# BSPD.net
KiCad netlist of a schematic drawn in Altium Designer
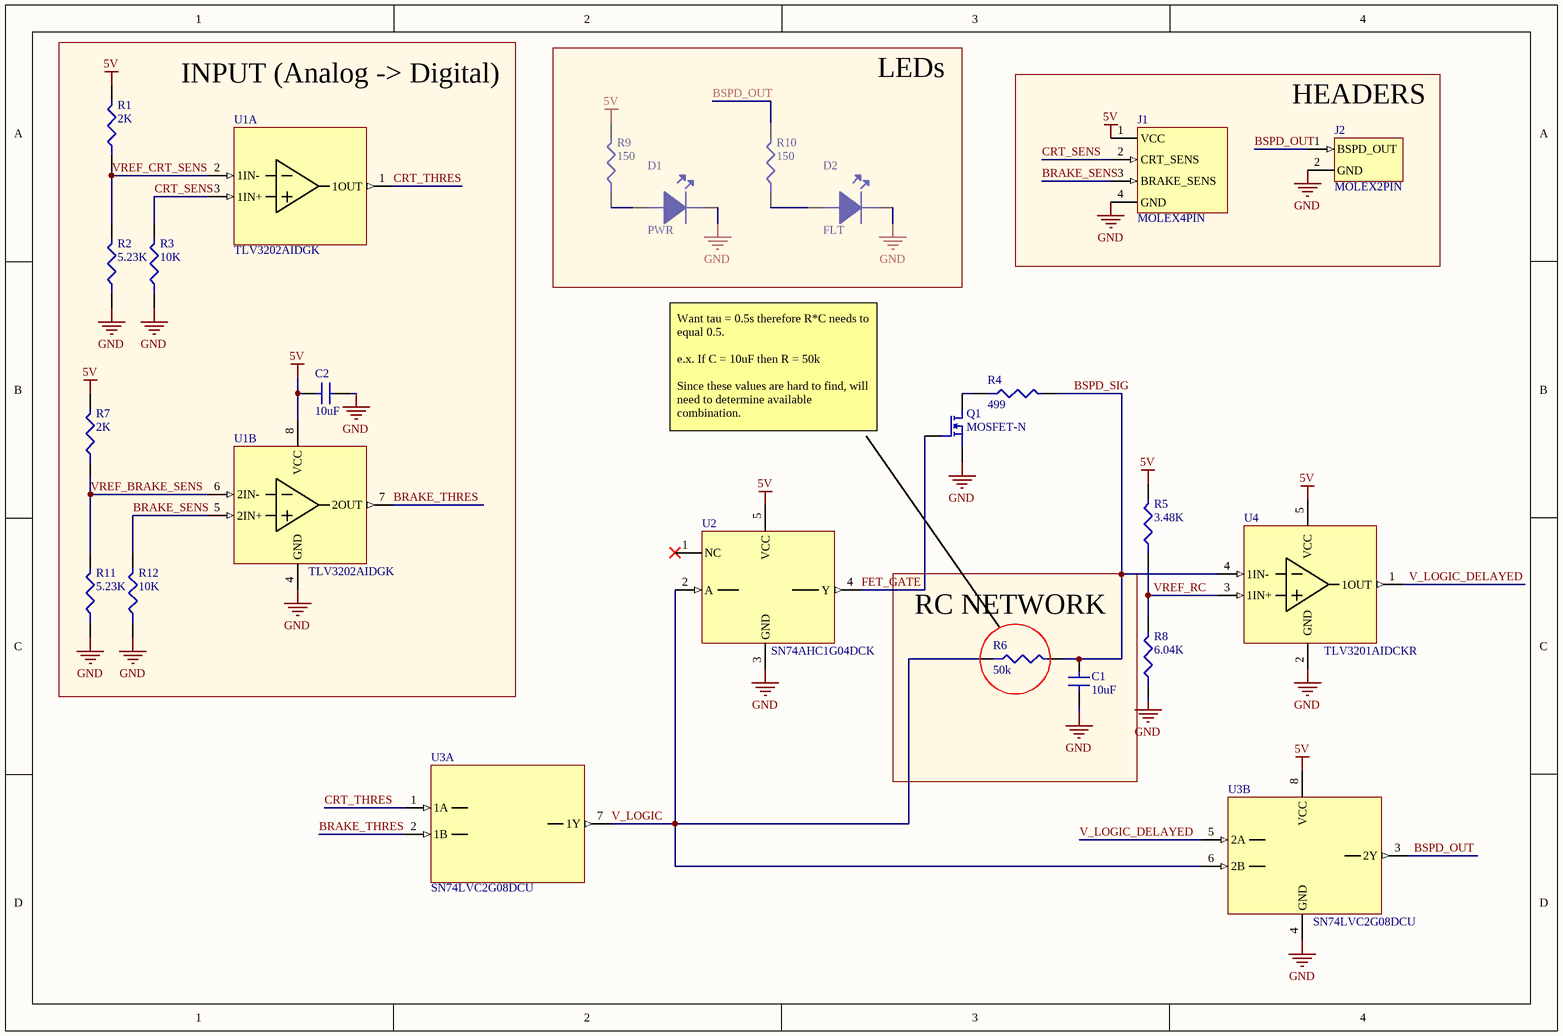
[diagram p0: BSPD.SchDoc]

(export (version "E")
  (design (tool "Eeschema 10.0.6"))
  (components
    (comp (ref "C1")
      (value "10uF")
      (footprint "C0805")
      (description "Cap Ceramic 10uF 10V X5R 10% SMD 0805 85C Embossed T/R")
      (fields
        (field (name "MANUFACTURER") "Samsung")
        (field (name "MANUFACTURER PART NUMBER") "CL21A106KPFNNNG")
      )
      (libsource (lib "BSPD") (part "CL21A106KPFNNNG"))
    )
    (comp (ref "C2")
      (value "10uF")
      (footprint "C0805")
      (description "Cap Ceramic 10uF 10V X5R 10% SMD 0805 85C Embossed T/R")
      (fields
        (field (name "MANUFACTURER") "Samsung")
        (field (name "MANUFACTURER PART NUMBER") "CL21A106KPFNNNG")
      )
      (libsource (lib "BSPD") (part "CL21A106KPFNNNG"))
    )
    (comp (ref "D1")
      (value "PWR")
      (footprint "LED_0603")
      (description "LED GREEN CLEAR SMD")
      (fields
        (field (name "MANUFACTURER") "Vishay Lite-On")
        (field (name "MANUFACTURER PART NUMBER") "LTST-C191KGKT")
      )
      (libsource (lib "BSPD") (part "LTST-C191KGKT"))
    )
    (comp (ref "D2")
      (value "FLT")
      (footprint "LED_0603")
      (description "LED RED CLEAR SMD")
      (fields
        (field (name "MANUFACTURER") "Vishay Lite-On")
        (field (name "MANUFACTURER PART NUMBER") "LTST-C191KRKT")
      )
      (libsource (lib "BSPD") (part "LTST-C191KRKT"))
    )
    (comp (ref "J1")
      (value "MOLEX4PIN")
      (footprint "MOLEX_4PIN")
      (fields (field (name "MANUFACTURER") "Molex") (field (name "MANUFACTURER PART NUMBER") "43650-0400"))
      (libsource (lib "BSPD") (part "43650-0400"))
    )
    (comp (ref "J2")
      (value "MOLEX2PIN")
      (footprint "MOLEX_2PIN")
      (description "Headers & Wire Housings R/A HEADER 2 POS TIN SINGLE ROW")
      (fields (field (name "MANUFACTURER") "Molex") (field (name "MANUFACTURER PART NUMBER") "43650-0200"))
      (libsource (lib "BSPD") (part "43650-0200"))
    )
    (comp (ref "Q1")
      (value "MOSFET-N")
      (footprint "MOSFET")
      (description "MOSFET N-CH 50V 200MA SOT-23")
      (fields
        (field (name "MANUFACTURER") "ON Semiconductor")
        (field (name "MANUFACTURER PART NUMBER") "BSS138LT3G")
      )
      (libsource (lib "BSPD") (part "BSS138LT3G"))
    )
    (comp (ref "R1")
      (value "2K")
      (footprint "R0805")
      (description "RES SMD 2K OHM 0.1% 1/8W 0805")
      (fields
        (field (name "MANUFACTURER") "Panasonic")
        (field (name "MANUFACTURER PART NUMBER") "ERA6AEB202V")
      )
      (libsource (lib "BSPD") (part "ERA6AEB202V"))
    )
    (comp (ref "R2")
      (value "5.23K")
      (footprint "R0805")
      (description "RES SMD 5.23K OHM 0.1% 1/8W 0805")
      (fields
        (field (name "MANUFACTURER") "Panasonic")
        (field (name "MANUFACTURER PART NUMBER") "ERA6AEB5231V")
      )
      (libsource (lib "BSPD") (part "ERA6AEB5231V"))
    )
    (comp (ref "R3")
      (value "10K")
      (footprint "R0805")
      (description "RES SMD 10K OHM 0.1% 1/8W 0805")
      (fields
        (field (name "MANUFACTURER") "Panasonic")
        (field (name "MANUFACTURER PART NUMBER") "ERA6AEB103V")
      )
      (libsource (lib "BSPD") (part "ERA6AEB103V"))
    )
    (comp (ref "R4")
      (value "499")
      (footprint "R0805")
      (description "RES SMD 499 OHM 0.1% 1/8W 0805")
      (fields
        (field (name "MANUFACTURER") "Panasonic")
        (field (name "MANUFACTURER PART NUMBER") "ERA-6AEB4990V")
      )
      (libsource (lib "BSPD") (part "ERA-6AEB4990V"))
    )
    (comp (ref "R5")
      (value "3.48K")
      (footprint "R0805")
      (description "RES SMD 348K OHM 0.1% 1/8W 0805")
      (fields
        (field (name "MANUFACTURER") "Panasonic")
        (field (name "MANUFACTURER PART NUMBER") "ERA6AEB3483V")
      )
      (libsource (lib "BSPD") (part "ERA6AEB3483V"))
    )
    (comp (ref "R6")
      (value "50k")
      (footprint "RESC2013X12N")
      (description "RES 50K OHM 0.1% 1/5W 0805")
      (fields
        (field (name "MANUFACTURER") "Vishay")
        (field (name "MANUFACTURER PART NUMBER") "PTN0805E5002BST1")
      )
      (libsource (lib "BSPD") (part "PTN0805E5002BST1"))
    )
    (comp (ref "R7")
      (value "2K")
      (footprint "R0805")
      (description "RES SMD 2K OHM 0.1% 1/8W 0805")
      (fields
        (field (name "MANUFACTURER") "Panasonic")
        (field (name "MANUFACTURER PART NUMBER") "ERA6AEB202V")
      )
      (libsource (lib "BSPD") (part "ERA6AEB202V"))
    )
    (comp (ref "R8")
      (value "6.04K")
      (footprint "R0805")
      (description "RES SMD 6.04K OHM 0.1% 1/8W 0805")
      (fields
        (field (name "MANUFACTURER") "Panasonic")
        (field (name "MANUFACTURER PART NUMBER") "ERA6AEB6041V")
      )
      (libsource (lib "BSPD") (part "ERA6AEB6041V"))
    )
    (comp (ref "R9")
      (value "150")
      (footprint "RESC2012X07N")
      (description "RES SMD 150 OHM 1% 1/8W 0805")
      (fields
        (field (name "MANUFACTURER") "Panasonic")
        (field (name "MANUFACTURER PART NUMBER") "ERJ6ENF1500V")
      )
      (libsource (lib "BSPD") (part "ERJ6ENF1500V"))
    )
    (comp (ref "R10")
      (value "150")
      (footprint "RESC2012X07N")
      (description "RES SMD 150 OHM 1% 1/8W 0805")
      (fields
        (field (name "MANUFACTURER") "Panasonic")
        (field (name "MANUFACTURER PART NUMBER") "ERJ6ENF1500V")
      )
      (libsource (lib "BSPD") (part "ERJ6ENF1500V"))
    )
    (comp (ref "R11")
      (value "5.23K")
      (footprint "R0805")
      (description "RES SMD 5.23K OHM 0.1% 1/8W 0805")
      (fields
        (field (name "MANUFACTURER") "Panasonic")
        (field (name "MANUFACTURER PART NUMBER") "ERA6AEB5231V")
      )
      (libsource (lib "BSPD") (part "ERA6AEB5231V"))
    )
    (comp (ref "R12")
      (value "10K")
      (footprint "R0805")
      (description "RES SMD 10K OHM 0.1% 1/8W 0805")
      (fields
        (field (name "MANUFACTURER") "Panasonic")
        (field (name "MANUFACTURER PART NUMBER") "ERA6AEB103V")
      )
      (libsource (lib "BSPD") (part "ERA6AEB103V"))
    )
    (comp (ref "U1")
      (value "TLV3202AIDGK")
      (footprint "TLV3202AIDGK")
      (description "IC COMPAR PWR RRI DL PP 8VSSOP")
      (fields (field (name "MANUFACTURER") "Texas Instruments"))
      (libsource (lib "BSPD") (part "TLV3202AIDGK"))
    )
    (comp (ref "U2")
      (value "SN74AHC1G04DCK")
      (footprint "SN74AHC1G04DCK")
      (description "The SN74AHC1G04 contains one inverter gate. The\r\ndevice performs the Boolean function Y = A bar.")
      (fields
        (field (name "MANUFACTURER") "Texas Instruments")
        (field (name "MANUFACTURER PART NUMBER") "SN74AHC1G04DCKR")
      )
      (libsource (lib "BSPD") (part "SN74AHC1G04DCK"))
    )
    (comp (ref "U3")
      (value "SN74LVC2G08DCU")
      (footprint "SN74LVC2G08DCUR")
      (description "Dual 2-Input Positive-AND Gate")
      (libsource (lib "BSPD") (part "SN74LVC2G08DCUR"))
    )
    (comp (ref "U4")
      (value "TLV3201AIDCKR")
      (footprint "TLV3201AIDCK")
      (description "Comparator Single R-R I/P 5.5V 5-Pin SC-70 T/R")
      (fields (field (name "MANUFACTURER") "Texas Instruments"))
      (libsource (lib "BSPD") (part "TLV3201AIDCKR"))
    )
  )
  (nets
    (net (code "1") (name "/BRAKE_SENS") (class "Default")
      (node (ref "J1") (pin "3") (pinfunction "BRAKE_SENS_3") (pintype "input"))
      (node (ref "R12") (pin "2") (pinfunction "2_2") (pintype "passive"))
      (node (ref "U1") (pin "5") (pinfunction "2IN+_5") (pintype "input"))
    )
    (net (code "2") (name "/BRAKE_THRES") (class "Default")
      (node (ref "U1") (pin "7") (pinfunction "2OUT_7") (pintype "output"))
      (node (ref "U3") (pin "2") (pinfunction "1B_2") (pintype "input"))
    )
    (net (code "3") (name "/BSPD_OUT") (class "Default")
      (node (ref "J2") (pin "1") (pinfunction "BSPD_OUT_1") (pintype "input"))
      (node (ref "R10") (pin "2") (pinfunction "2_2") (pintype "passive"))
      (node (ref "U3") (pin "3") (pinfunction "2Y_3") (pintype "output"))
    )
    (net (code "4") (name "/BSPD_SIG") (class "Default")
      (node (ref "C1") (pin "2") (pinfunction "2_2") (pintype "passive"))
      (node (ref "R4") (pin "2") (pinfunction "2_2") (pintype "passive"))
      (node (ref "R6") (pin "2") (pinfunction "2_2") (pintype "passive"))
      (node (ref "U4") (pin "4") (pinfunction "1IN-_4") (pintype "input"))
    )
    (net (code "5") (name "/CRT_SENS") (class "Default")
      (node (ref "J1") (pin "2") (pinfunction "CRT_SENS_2") (pintype "input"))
      (node (ref "R3") (pin "2") (pinfunction "2_2") (pintype "passive"))
      (node (ref "U1") (pin "3") (pinfunction "1IN+_3") (pintype "input"))
    )
    (net (code "6") (name "/CRT_THRES") (class "Default")
      (node (ref "U1") (pin "1") (pinfunction "1OUT_1") (pintype "output"))
      (node (ref "U3") (pin "1") (pinfunction "1A_1") (pintype "input"))
    )
    (net (code "7") (name "/FET_GATE") (class "Default")
      (node (ref "Q1") (pin "1") (pinfunction "1_1") (pintype "passive"))
      (node (ref "U2") (pin "4") (pinfunction "Y_4") (pintype "output"))
    )
    (net (code "8") (name "/VREF_BRAKE_SENS") (class "Default")
      (node (ref "R11") (pin "2") (pinfunction "2_2") (pintype "passive"))
      (node (ref "R7") (pin "1") (pinfunction "1_1") (pintype "passive"))
      (node (ref "U1") (pin "6") (pinfunction "2IN-_6") (pintype "input"))
    )
    (net (code "9") (name "/VREF_CRT_SENS") (class "Default")
      (node (ref "R1") (pin "1") (pinfunction "1_1") (pintype "passive"))
      (node (ref "R2") (pin "2") (pinfunction "2_2") (pintype "passive"))
      (node (ref "U1") (pin "2") (pinfunction "1IN-_2") (pintype "input"))
    )
    (net (code "10") (name "/VREF_RC") (class "Default")
      (node (ref "R5") (pin "1") (pinfunction "1_1") (pintype "passive"))
      (node (ref "R8") (pin "2") (pinfunction "2_2") (pintype "passive"))
      (node (ref "U4") (pin "3") (pinfunction "1IN+_3") (pintype "input"))
    )
    (net (code "11") (name "/V_LOGIC") (class "Default")
      (node (ref "R6") (pin "1") (pinfunction "1_1") (pintype "passive"))
      (node (ref "U2") (pin "2") (pinfunction "A_2") (pintype "input"))
      (node (ref "U3") (pin "6") (pinfunction "2B_6") (pintype "input"))
      (node (ref "U3") (pin "7") (pinfunction "1Y_7") (pintype "output"))
    )
    (net (code "12") (name "/V_LOGIC_DELAYED") (class "Default")
      (node (ref "U3") (pin "5") (pinfunction "2A_5") (pintype "input"))
      (node (ref "U4") (pin "1") (pinfunction "1OUT_1") (pintype "output"))
    )
    (net (code "13") (name "5V") (class "Default")
      (node (ref "C2") (pin "2") (pinfunction "2_2") (pintype "passive"))
      (node (ref "J1") (pin "1") (pinfunction "VCC_1") (pintype "power_in"))
      (node (ref "R1") (pin "2") (pinfunction "2_2") (pintype "passive"))
      (node (ref "R5") (pin "2") (pinfunction "2_2") (pintype "passive"))
      (node (ref "R7") (pin "2") (pinfunction "2_2") (pintype "passive"))
      (node (ref "R9") (pin "2") (pinfunction "2_2") (pintype "passive"))
      (node (ref "U1") (pin "8") (pinfunction "VCC_8") (pintype "power_in"))
      (node (ref "U2") (pin "5") (pinfunction "VCC_5") (pintype "power_in"))
      (node (ref "U3") (pin "8") (pinfunction "VCC_8") (pintype "power_in"))
      (node (ref "U4") (pin "5") (pinfunction "VCC_5") (pintype "power_in"))
    )
    (net (code "14") (name "GND") (class "Default")
      (node (ref "C1") (pin "1") (pinfunction "1_1") (pintype "passive"))
      (node (ref "C2") (pin "1") (pinfunction "1_1") (pintype "passive"))
      (node (ref "D1") (pin "2") (pinfunction "2_2") (pintype "passive"))
      (node (ref "D2") (pin "2") (pinfunction "2_2") (pintype "passive"))
      (node (ref "J1") (pin "4") (pinfunction "GND_4") (pintype "power_in"))
      (node (ref "J2") (pin "2") (pinfunction "GND_2") (pintype "power_in"))
      (node (ref "Q1") (pin "2") (pinfunction "2_2") (pintype "passive"))
      (node (ref "R11") (pin "1") (pinfunction "1_1") (pintype "passive"))
      (node (ref "R12") (pin "1") (pinfunction "1_1") (pintype "passive"))
      (node (ref "R2") (pin "1") (pinfunction "1_1") (pintype "passive"))
      (node (ref "R3") (pin "1") (pinfunction "1_1") (pintype "passive"))
      (node (ref "R8") (pin "1") (pinfunction "1_1") (pintype "passive"))
      (node (ref "U1") (pin "4") (pinfunction "GND_4") (pintype "power_in"))
      (node (ref "U2") (pin "3") (pinfunction "GND_3") (pintype "power_in"))
      (node (ref "U3") (pin "4") (pinfunction "GND_4") (pintype "power_in"))
      (node (ref "U4") (pin "2") (pinfunction "GND_2") (pintype "power_in"))
    )
    (net (code "15") (name "Net-(D1-Pad1)") (class "Default")
      (node (ref "D1") (pin "1") (pinfunction "1_1") (pintype "passive"))
      (node (ref "R9") (pin "1") (pinfunction "1_1") (pintype "passive"))
    )
    (net (code "16") (name "Net-(D2-Pad1)") (class "Default")
      (node (ref "D2") (pin "1") (pinfunction "1_1") (pintype "passive"))
      (node (ref "R10") (pin "1") (pinfunction "1_1") (pintype "passive"))
    )
    (net (code "17") (name "Net-(Q1-Pad3)") (class "Default")
      (node (ref "Q1") (pin "3") (pinfunction "3_3") (pintype "passive"))
      (node (ref "R4") (pin "1") (pinfunction "1_1") (pintype "passive"))
    )
    (net (code "18") (name "unconnected-(U2-NC-Pad1)") (class "Default")
      (node (ref "U2") (pin "1") (pinfunction "NC_1") (pintype "open_collector+no_connect"))
    )
  )
)
